# TSOC_Teensy3X.net
KiCad netlist of a schematic drawn in EAGLE
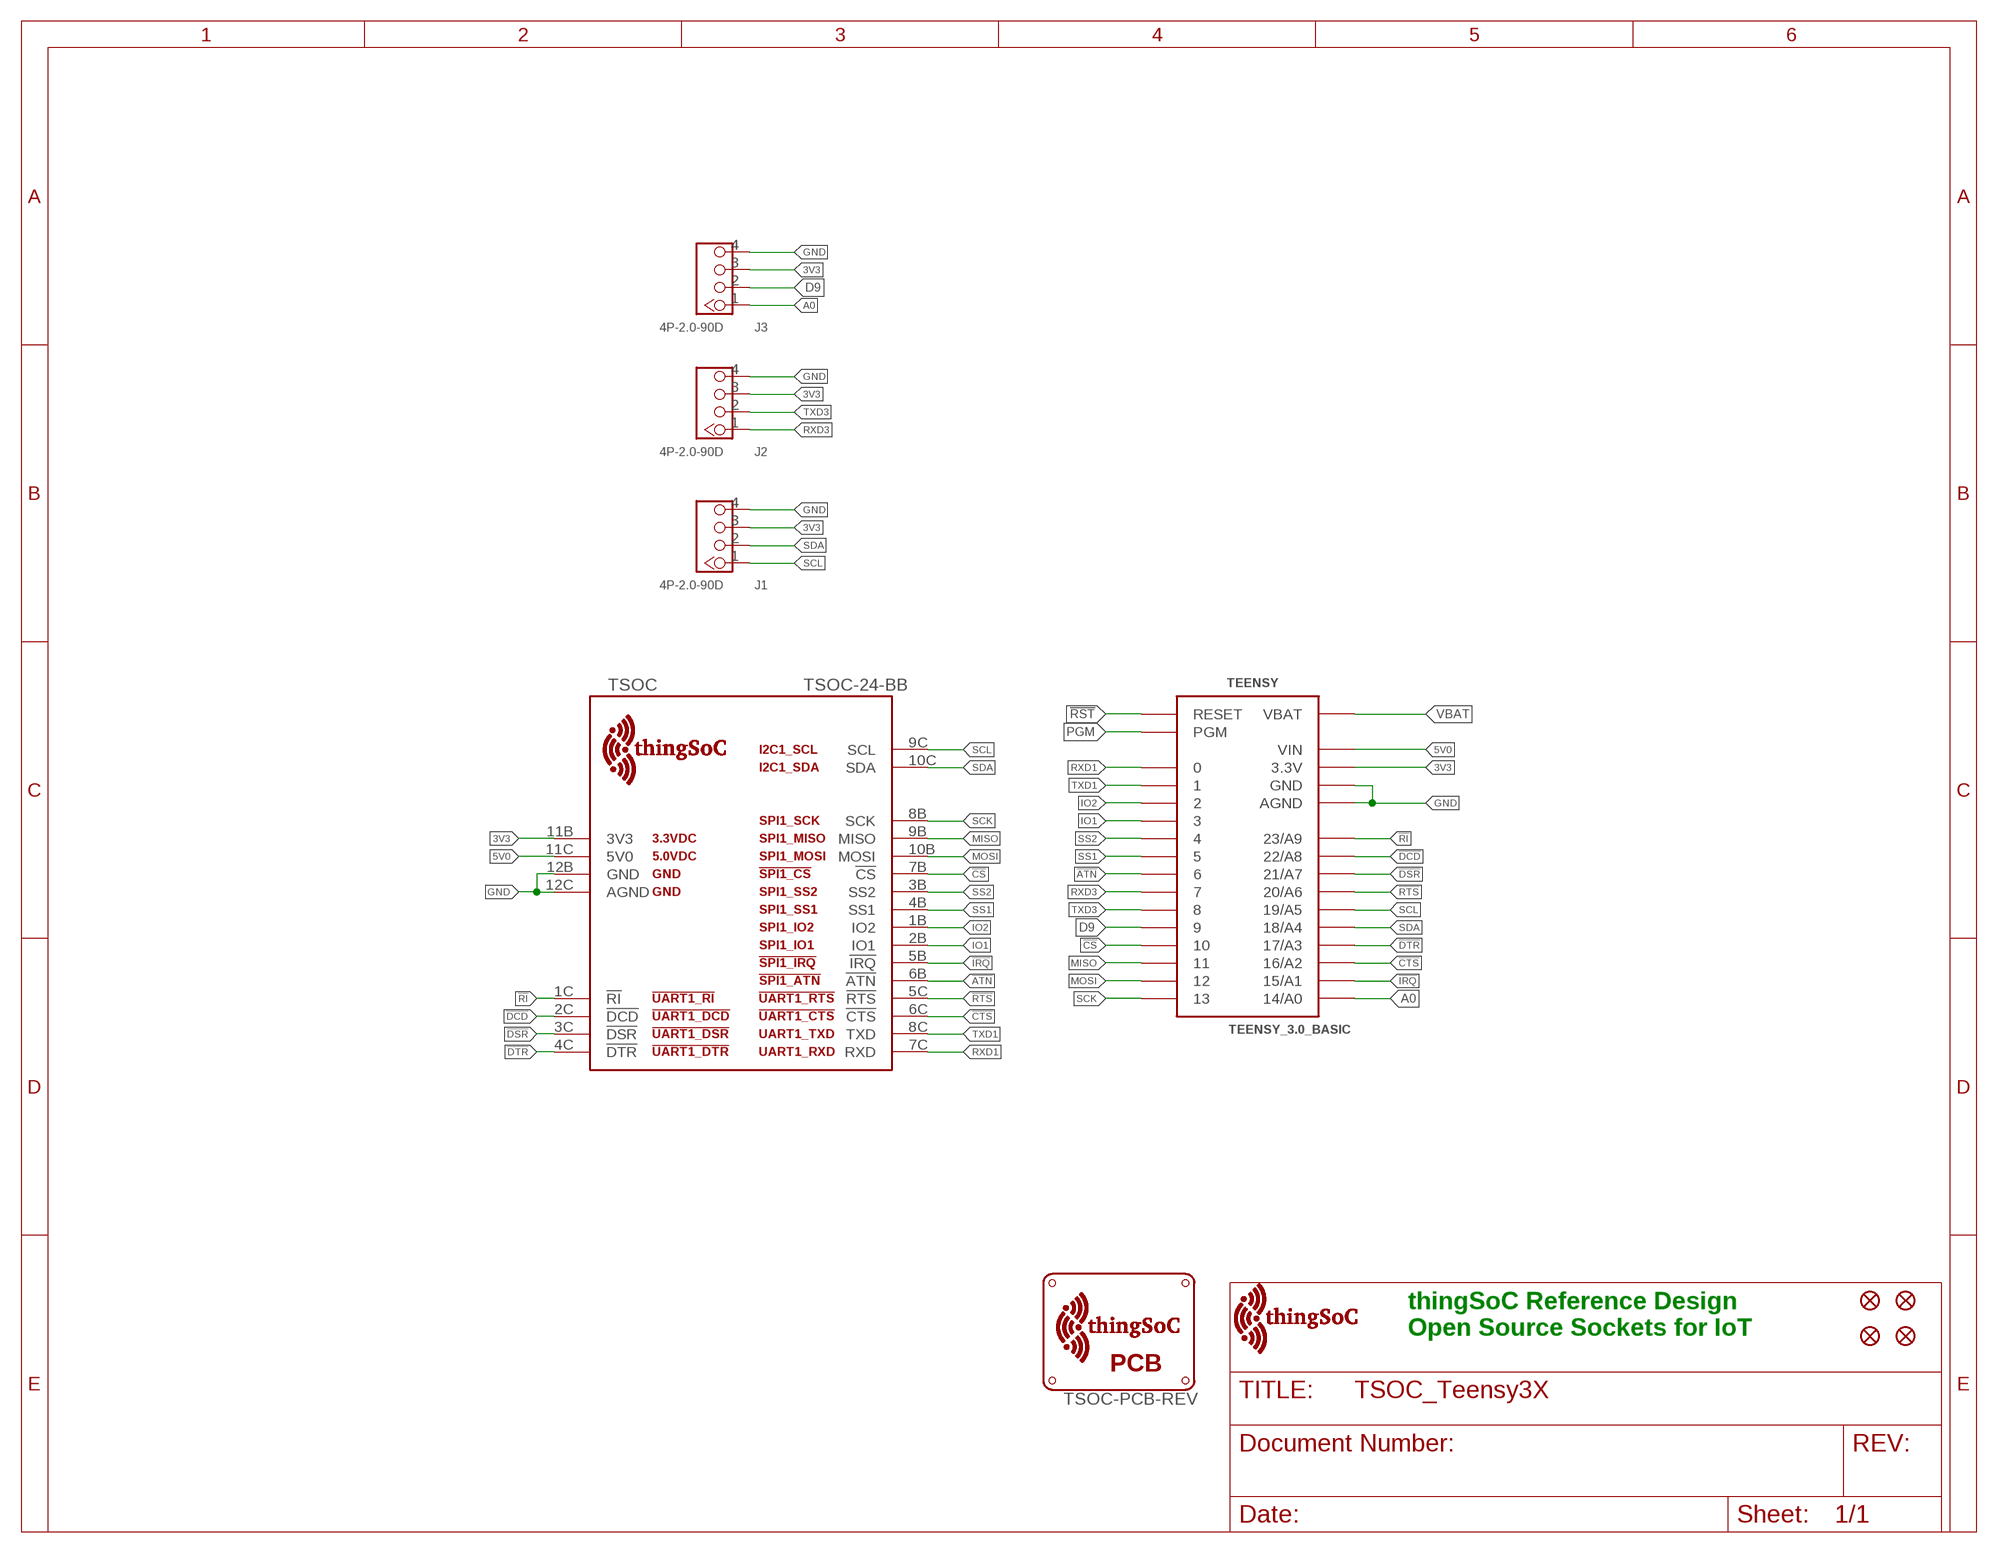
[diagram p0: schematic, sheet 1]

(export (version "E")
  (design (tool "Eeschema 10.0.6"))
  (components
    (comp (ref "FID1")
      (value "FIDUCIALUFIDUCIAL")
      (footprint "eagle-import:MICRO-FIDUCIAL")
      (libsource (lib "eagle-import") (part "FIDUCIALUFIDUCIAL"))
    )
    (comp (ref "FID2")
      (value "FIDUCIALUFIDUCIAL")
      (footprint "eagle-import:MICRO-FIDUCIAL")
      (libsource (lib "eagle-import") (part "FIDUCIALUFIDUCIAL"))
    )
    (comp (ref "FID3")
      (value "FIDUCIALUFIDUCIAL")
      (footprint "eagle-import:MICRO-FIDUCIAL")
      (libsource (lib "eagle-import") (part "FIDUCIALUFIDUCIAL"))
    )
    (comp (ref "FID4")
      (value "FIDUCIALUFIDUCIAL")
      (footprint "eagle-import:MICRO-FIDUCIAL")
      (libsource (lib "eagle-import") (part "FIDUCIALUFIDUCIAL"))
    )
    (comp (ref "J1")
      (value "4P-2.0-90D")
      (footprint "eagle-import:HW4-2.0-90D")
      (libsource (lib "eagle-import") (part "GROVE-CONNECTOR-DIP-90D(4P-2.0)"))
    )
    (comp (ref "J2")
      (value "4P-2.0-90D")
      (footprint "eagle-import:HW4-2.0-90D")
      (libsource (lib "eagle-import") (part "GROVE-CONNECTOR-DIP-90D(4P-2.0)"))
    )
    (comp (ref "J3")
      (value "4P-2.0-90D")
      (footprint "eagle-import:HW4-2.0-90D")
      (libsource (lib "eagle-import") (part "GROVE-CONNECTOR-DIP-90D(4P-2.0)"))
    )
    (comp (ref "TEENSY")
      (value "TEENSY_3.0_BASIC")
      (footprint "eagle-import:TEENSY_3.0_BASIC")
      (libsource (lib "eagle-import") (part "TEENSY_3.0_BASIC"))
    )
    (comp (ref "TSOC")
      (value "TSOC-24-BB")
      (footprint "eagle-import:TSOC-BB-S24")
      (libsource (lib "eagle-import") (part "TSOC-24-BB"))
    )
    (comp (ref "U$2")
      (value "TSOC-PCB-REV")
      (footprint "eagle-import:TSOC-BB-BRD-PLUS-CUT-REV")
      (libsource (lib "eagle-import") (part "TSOC-PCB-REV"))
    )
    (comp (ref "U$5")
      (value "TSOC-LOGO-LRG")
      (footprint "eagle-import:TSOC-LOGO-LRG")
      (libsource (lib "eagle-import") (part "TSOC-LOGO-LRG"))
    )
  )
  (nets
    (net (code "1") (name "/~{ATN}") (class "Default")
      (node (ref "TEENSY") (pin "6") (pinfunction "6_6") (pintype "bidirectional"))
      (node (ref "TSOC") (pin "6B") (pinfunction "~{ATN}_6B") (pintype "bidirectional"))
    )
    (net (code "2") (name "/~{CS}") (class "Default")
      (node (ref "TEENSY") (pin "10") (pinfunction "10_10") (pintype "bidirectional"))
      (node (ref "TSOC") (pin "7B") (pinfunction "~{CS}_7B") (pintype "bidirectional"))
    )
    (net (code "3") (name "/~{CTS}") (class "Default")
      (node (ref "TEENSY") (pin "16/A2") (pinfunction "16/A2_16/A2") (pintype "bidirectional"))
      (node (ref "TSOC") (pin "6C") (pinfunction "~{CTS}_6C") (pintype "bidirectional"))
    )
    (net (code "4") (name "/~{DCD}") (class "Default")
      (node (ref "TEENSY") (pin "22/A8") (pinfunction "22/A8_22/A8") (pintype "bidirectional"))
      (node (ref "TSOC") (pin "2C") (pinfunction "~{DCD}_2C") (pintype "bidirectional"))
    )
    (net (code "5") (name "/~{DSR}") (class "Default")
      (node (ref "TEENSY") (pin "21/A7") (pinfunction "21/A7_21/A7") (pintype "bidirectional"))
      (node (ref "TSOC") (pin "3C") (pinfunction "~{DSR}_3C") (pintype "bidirectional"))
    )
    (net (code "6") (name "/~{DTR}") (class "Default")
      (node (ref "TEENSY") (pin "17/A3") (pinfunction "17/A3_17/A3") (pintype "bidirectional"))
      (node (ref "TSOC") (pin "4C") (pinfunction "~{DTR}_4C") (pintype "bidirectional"))
    )
    (net (code "7") (name "/~{IRQ}") (class "Default")
      (node (ref "TEENSY") (pin "15/A1") (pinfunction "15/A1_15/A1") (pintype "bidirectional"))
      (node (ref "TSOC") (pin "5B") (pinfunction "~{IRQ}_5B") (pintype "bidirectional"))
    )
    (net (code "8") (name "/~{RI}") (class "Default")
      (node (ref "TEENSY") (pin "23/A9") (pinfunction "23/A9_23/A9") (pintype "bidirectional"))
      (node (ref "TSOC") (pin "1C") (pinfunction "~{RI}_1C") (pintype "bidirectional"))
    )
    (net (code "9") (name "/~{RST}") (class "Default")
      (node (ref "TEENSY") (pin "RESET") (pinfunction "RESET_RESET") (pintype "bidirectional"))
    )
    (net (code "10") (name "/~{RTS}") (class "Default")
      (node (ref "TEENSY") (pin "20/A6") (pinfunction "20/A6_20/A6") (pintype "bidirectional"))
      (node (ref "TSOC") (pin "5C") (pinfunction "~{RTS}_5C") (pintype "bidirectional"))
    )
    (net (code "11") (name "3V3") (class "Default")
      (node (ref "J1") (pin "3") (pinfunction "3_3") (pintype "bidirectional"))
      (node (ref "J2") (pin "3") (pinfunction "3_3") (pintype "bidirectional"))
      (node (ref "J3") (pin "3") (pinfunction "3_3") (pintype "bidirectional"))
      (node (ref "TEENSY") (pin "3.3V") (pinfunction "3.3V_3.3V") (pintype "power_in"))
      (node (ref "TEENSY") (pin "3.3V1") (pinfunction "3.3V_3.3V1") (pintype "power_in"))
      (node (ref "TSOC") (pin "11B") (pinfunction "3V3_11B") (pintype "bidirectional"))
    )
    (net (code "12") (name "5V0") (class "Default")
      (node (ref "TEENSY") (pin "VIN") (pinfunction "VIN_VIN") (pintype "power_in"))
      (node (ref "TSOC") (pin "11C") (pinfunction "5V0_11C") (pintype "bidirectional"))
    )
    (net (code "13") (name "A0") (class "Default")
      (node (ref "J3") (pin "1") (pinfunction "1_1") (pintype "bidirectional"))
      (node (ref "TEENSY") (pin "14/A0") (pinfunction "14/A0_14/A0") (pintype "bidirectional"))
    )
    (net (code "14") (name "D9") (class "Default")
      (node (ref "J3") (pin "2") (pinfunction "2_2") (pintype "bidirectional"))
      (node (ref "TEENSY") (pin "9") (pinfunction "9_9") (pintype "bidirectional"))
    )
    (net (code "15") (name "GND") (class "Default")
      (node (ref "J1") (pin "4") (pinfunction "4_4") (pintype "bidirectional"))
      (node (ref "J2") (pin "4") (pinfunction "4_4") (pintype "bidirectional"))
      (node (ref "J3") (pin "4") (pinfunction "4_4") (pintype "bidirectional"))
      (node (ref "TEENSY") (pin "AGND") (pinfunction "AGND_AGND") (pintype "power_in"))
      (node (ref "TEENSY") (pin "GND") (pinfunction "GND_GND") (pintype "power_in"))
      (node (ref "TEENSY") (pin "GND1") (pinfunction "GND_GND1") (pintype "power_in"))
      (node (ref "TSOC") (pin "12B") (pinfunction "GND_12B") (pintype "bidirectional"))
      (node (ref "TSOC") (pin "12C") (pinfunction "AGND_12C") (pintype "bidirectional"))
    )
    (net (code "16") (name "IO1") (class "Default")
      (node (ref "TEENSY") (pin "3") (pinfunction "3_3") (pintype "bidirectional"))
      (node (ref "TSOC") (pin "2B") (pinfunction "IO1_2B") (pintype "bidirectional"))
    )
    (net (code "17") (name "IO2") (class "Default")
      (node (ref "TEENSY") (pin "2") (pinfunction "2_2") (pintype "bidirectional"))
      (node (ref "TSOC") (pin "1B") (pinfunction "IO2_1B") (pintype "bidirectional"))
    )
    (net (code "18") (name "MISO") (class "Default")
      (node (ref "TEENSY") (pin "11") (pinfunction "11_11") (pintype "bidirectional"))
      (node (ref "TSOC") (pin "9B") (pinfunction "MISO_9B") (pintype "bidirectional"))
    )
    (net (code "19") (name "MOSI") (class "Default")
      (node (ref "TEENSY") (pin "12") (pinfunction "12_12") (pintype "bidirectional"))
      (node (ref "TSOC") (pin "10B") (pinfunction "MOSI_10B") (pintype "bidirectional"))
    )
    (net (code "20") (name "PGM") (class "Default")
      (node (ref "TEENSY") (pin "PGM") (pinfunction "PGM_PGM") (pintype "bidirectional"))
    )
    (net (code "21") (name "RXD1") (class "Default")
      (node (ref "TEENSY") (pin "0") (pinfunction "0_0") (pintype "bidirectional"))
      (node (ref "TSOC") (pin "7C") (pinfunction "RXD_7C") (pintype "bidirectional"))
    )
    (net (code "22") (name "RXD3") (class "Default")
      (node (ref "J2") (pin "1") (pinfunction "1_1") (pintype "bidirectional"))
      (node (ref "TEENSY") (pin "7") (pinfunction "7_7") (pintype "bidirectional"))
    )
    (net (code "23") (name "SCK") (class "Default")
      (node (ref "TEENSY") (pin "13") (pinfunction "13_13") (pintype "bidirectional"))
      (node (ref "TSOC") (pin "8B") (pinfunction "SCK_8B") (pintype "bidirectional"))
    )
    (net (code "24") (name "SCL") (class "Default")
      (node (ref "J1") (pin "1") (pinfunction "1_1") (pintype "bidirectional"))
      (node (ref "TEENSY") (pin "19/A5") (pinfunction "19/A5_19/A5") (pintype "bidirectional"))
      (node (ref "TSOC") (pin "9C") (pinfunction "SCL_9C") (pintype "bidirectional"))
    )
    (net (code "25") (name "SDA") (class "Default")
      (node (ref "J1") (pin "2") (pinfunction "2_2") (pintype "bidirectional"))
      (node (ref "TEENSY") (pin "18/A4") (pinfunction "18/A4_18/A4") (pintype "bidirectional"))
      (node (ref "TSOC") (pin "10C") (pinfunction "SDA_10C") (pintype "bidirectional"))
    )
    (net (code "26") (name "SS1") (class "Default")
      (node (ref "TEENSY") (pin "5") (pinfunction "5_5") (pintype "bidirectional"))
      (node (ref "TSOC") (pin "4B") (pinfunction "SS1_4B") (pintype "bidirectional"))
    )
    (net (code "27") (name "SS2") (class "Default")
      (node (ref "TEENSY") (pin "4") (pinfunction "4_4") (pintype "bidirectional"))
      (node (ref "TSOC") (pin "3B") (pinfunction "SS2_3B") (pintype "bidirectional"))
    )
    (net (code "28") (name "TXD1") (class "Default")
      (node (ref "TEENSY") (pin "1") (pinfunction "1_1") (pintype "bidirectional"))
      (node (ref "TSOC") (pin "8C") (pinfunction "TXD_8C") (pintype "bidirectional"))
    )
    (net (code "29") (name "TXD3") (class "Default")
      (node (ref "J2") (pin "2") (pinfunction "2_2") (pintype "bidirectional"))
      (node (ref "TEENSY") (pin "8") (pinfunction "8_8") (pintype "bidirectional"))
    )
    (net (code "30") (name "VBAT") (class "Default")
      (node (ref "TEENSY") (pin "VBAT") (pinfunction "VBAT_VBAT") (pintype "power_in"))
    )
  )
)
